# BPW5011-SPI-ADC.net
KiCad netlist of a schematic drawn in EAGLE
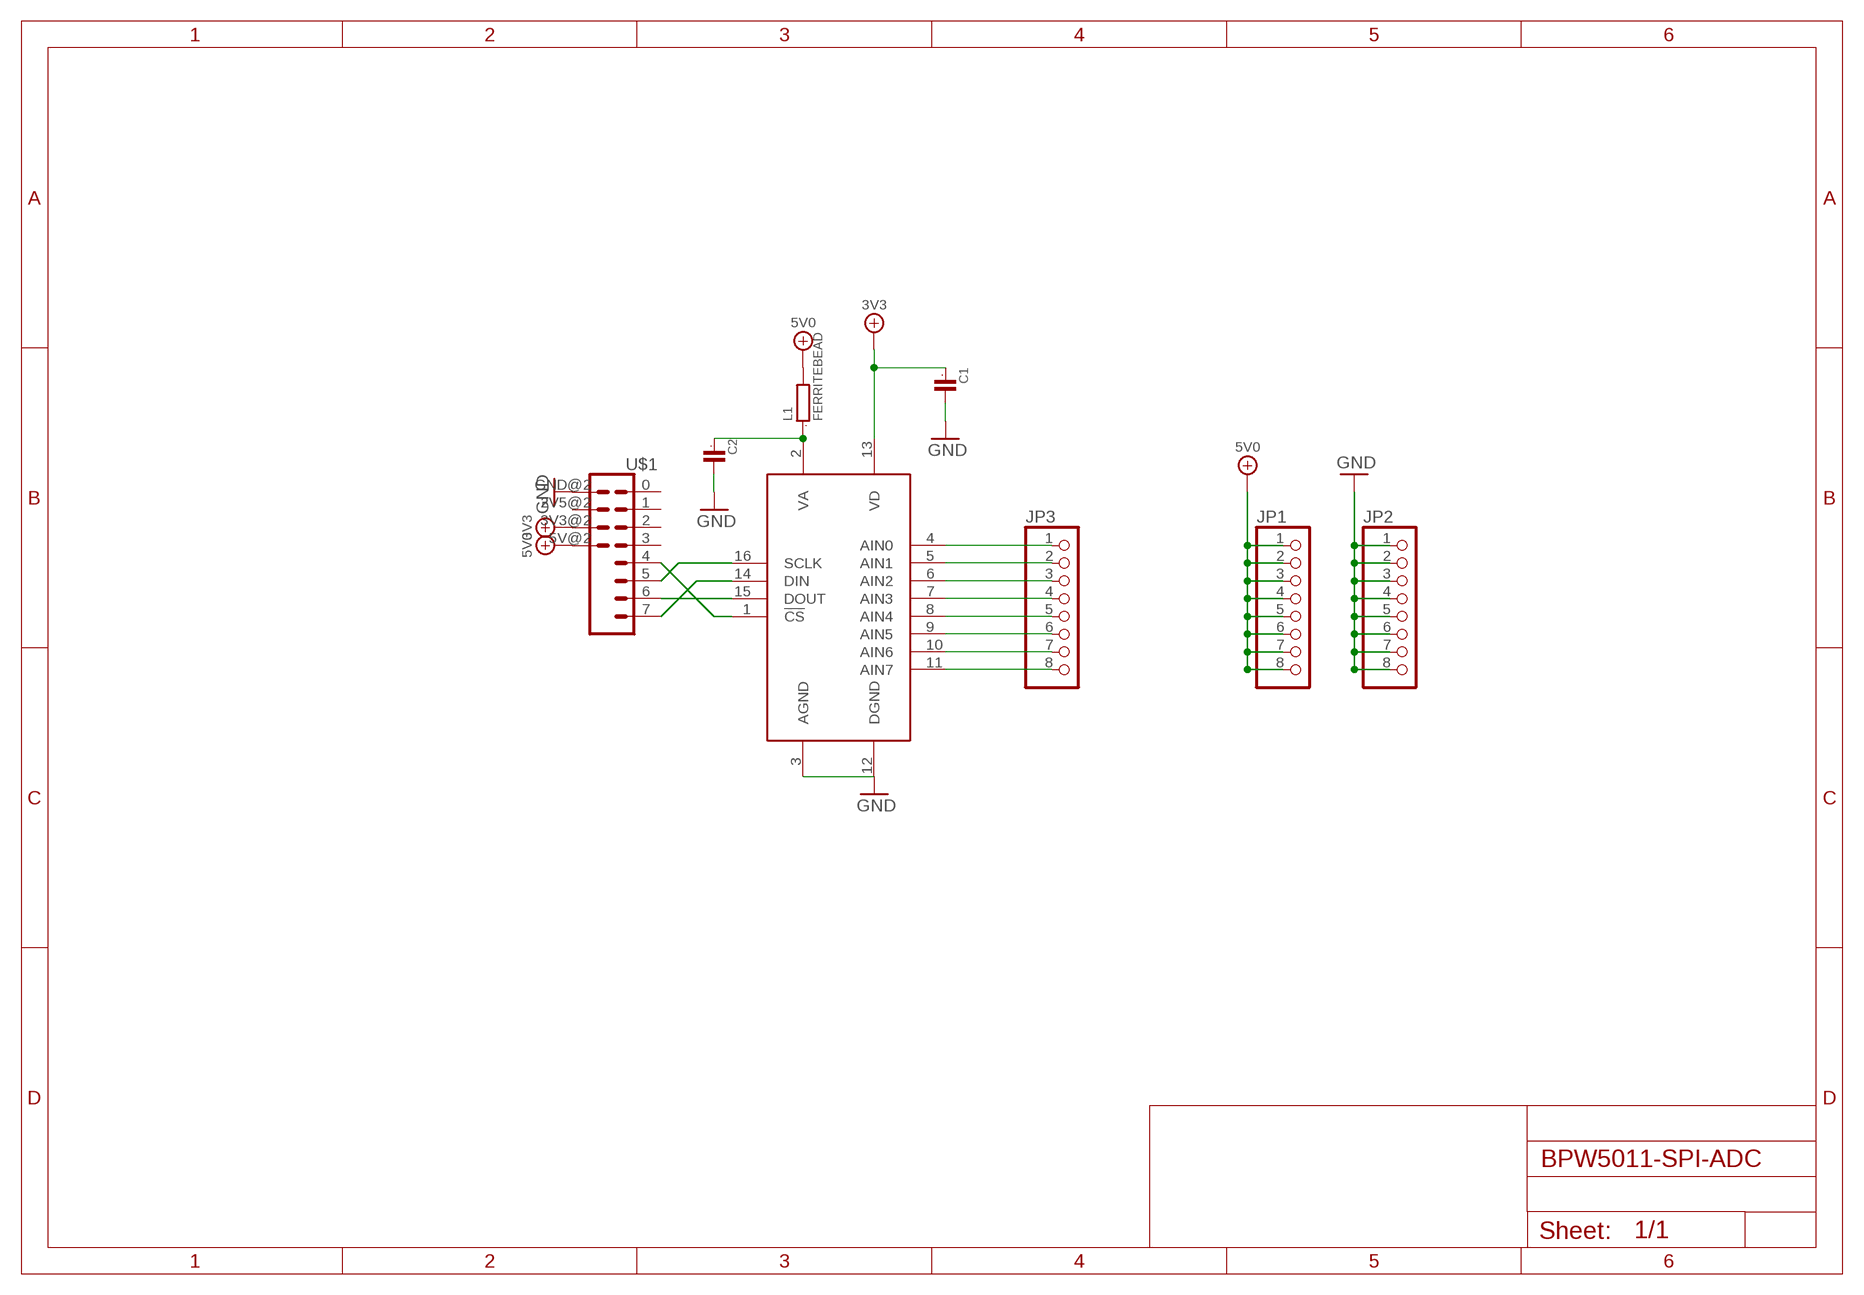
[diagram p0: schematic, sheet 1]

(export (version "E")
  (design (tool "Eeschema 10.0.6"))
  (components
    (comp (ref "C1")
      (value "C0603")
      (footprint "eagle-import:0603")
      (libsource (lib "eagle-import") (part "C0603"))
    )
    (comp (ref "C2")
      (value "C0603")
      (footprint "eagle-import:0603")
      (libsource (lib "eagle-import") (part "C0603"))
    )
    (comp (ref "JP1")
      (value "PINHD-1X8")
      (footprint "eagle-import:1X08")
      (libsource (lib "eagle-import") (part "PINHD-1X8"))
    )
    (comp (ref "JP2")
      (value "PINHD-1X8")
      (footprint "eagle-import:1X08")
      (libsource (lib "eagle-import") (part "PINHD-1X8"))
    )
    (comp (ref "JP3")
      (value "PINHD-1X8")
      (footprint "eagle-import:1X08")
      (libsource (lib "eagle-import") (part "PINHD-1X8"))
    )
    (comp (ref "L1")
      (value "FERRITEBEAD")
      (footprint "eagle-import:0603")
      (libsource (lib "eagle-import") (part "R0603"))
    )
    (comp (ref "U$1")
      (value "WING8WING8_NOHOLES")
      (footprint "eagle-import:WINGSIDE_8BIT_NOHOLES")
      (libsource (lib "eagle-import") (part "WING8WING8_NOHOLES"))
    )
    (comp (ref "U1")
      (value "ADC088S102CIMT")
      (footprint "eagle-import:TSSOP16")
      (libsource (lib "eagle-import") (part "ADC088S102CIMT"))
    )
  )
  (nets
    (net (code "1") (name "3V3") (class "Default")
      (node (ref "C1") (pin "1") (pinfunction "1_1") (pintype "passive"))
      (node (ref "U$1") (pin "3V3@2") (pinfunction "3V3_3V3@2") (pintype "passive"))
      (node (ref "U1") (pin "13") (pinfunction "VD_13") (pintype "power_in"))
    )
    (net (code "2") (name "5V0") (class "Default")
      (node (ref "JP1") (pin "1") (pinfunction "1_1") (pintype "passive"))
      (node (ref "JP1") (pin "2") (pinfunction "2_2") (pintype "passive"))
      (node (ref "JP1") (pin "3") (pinfunction "3_3") (pintype "passive"))
      (node (ref "JP1") (pin "4") (pinfunction "4_4") (pintype "passive"))
      (node (ref "JP1") (pin "5") (pinfunction "5_5") (pintype "passive"))
      (node (ref "JP1") (pin "6") (pinfunction "6_6") (pintype "passive"))
      (node (ref "JP1") (pin "7") (pinfunction "7_7") (pintype "passive"))
      (node (ref "JP1") (pin "8") (pinfunction "8_8") (pintype "passive"))
      (node (ref "L1") (pin "2") (pinfunction "2_2") (pintype "passive"))
      (node (ref "U$1") (pin "5V@2") (pinfunction "5V_5V@2") (pintype "passive"))
    )
    (net (code "3") (name "GND") (class "Default")
      (node (ref "C1") (pin "2") (pinfunction "2_2") (pintype "passive"))
      (node (ref "C2") (pin "2") (pinfunction "2_2") (pintype "passive"))
      (node (ref "JP2") (pin "1") (pinfunction "1_1") (pintype "passive"))
      (node (ref "JP2") (pin "2") (pinfunction "2_2") (pintype "passive"))
      (node (ref "JP2") (pin "3") (pinfunction "3_3") (pintype "passive"))
      (node (ref "JP2") (pin "4") (pinfunction "4_4") (pintype "passive"))
      (node (ref "JP2") (pin "5") (pinfunction "5_5") (pintype "passive"))
      (node (ref "JP2") (pin "6") (pinfunction "6_6") (pintype "passive"))
      (node (ref "JP2") (pin "7") (pinfunction "7_7") (pintype "passive"))
      (node (ref "JP2") (pin "8") (pinfunction "8_8") (pintype "passive"))
      (node (ref "U$1") (pin "GND@2") (pinfunction "GND_GND@2") (pintype "passive"))
      (node (ref "U1") (pin "12") (pinfunction "DGND_12") (pintype "power_in"))
      (node (ref "U1") (pin "3") (pinfunction "AGND_3") (pintype "power_in"))
    )
    (net (code "4") (name "Net-(U$1-5)") (class "Default")
      (node (ref "U$1") (pin "4") (pinfunction "5_4") (pintype "passive"))
      (node (ref "U1") (pin "1") (pinfunction "~{CS}_1") (pintype "input"))
    )
    (net (code "5") (name "Net-(U$1-6)") (class "Default")
      (node (ref "U$1") (pin "5") (pinfunction "6_5") (pintype "passive"))
      (node (ref "U1") (pin "16") (pinfunction "SCLK_16") (pintype "input"))
    )
    (net (code "6") (name "Net-(U$1-7)") (class "Default")
      (node (ref "U$1") (pin "6") (pinfunction "7_6") (pintype "passive"))
      (node (ref "U1") (pin "15") (pinfunction "DOUT_15") (pintype "output"))
    )
    (net (code "7") (name "Net-(U$1-8)") (class "Default")
      (node (ref "U$1") (pin "7") (pinfunction "8_7") (pintype "passive"))
      (node (ref "U1") (pin "14") (pinfunction "DIN_14") (pintype "input"))
    )
    (net (code "8") (name "Net-(U1-AIN0)") (class "Default")
      (node (ref "JP3") (pin "1") (pinfunction "1_1") (pintype "passive"))
      (node (ref "U1") (pin "4") (pinfunction "AIN0_4") (pintype "input"))
    )
    (net (code "9") (name "Net-(U1-AIN1)") (class "Default")
      (node (ref "JP3") (pin "2") (pinfunction "2_2") (pintype "passive"))
      (node (ref "U1") (pin "5") (pinfunction "AIN1_5") (pintype "input"))
    )
    (net (code "10") (name "Net-(U1-AIN2)") (class "Default")
      (node (ref "JP3") (pin "3") (pinfunction "3_3") (pintype "passive"))
      (node (ref "U1") (pin "6") (pinfunction "AIN2_6") (pintype "input"))
    )
    (net (code "11") (name "Net-(U1-AIN3)") (class "Default")
      (node (ref "JP3") (pin "4") (pinfunction "4_4") (pintype "passive"))
      (node (ref "U1") (pin "7") (pinfunction "AIN3_7") (pintype "input"))
    )
    (net (code "12") (name "Net-(U1-AIN4)") (class "Default")
      (node (ref "JP3") (pin "5") (pinfunction "5_5") (pintype "passive"))
      (node (ref "U1") (pin "8") (pinfunction "AIN4_8") (pintype "input"))
    )
    (net (code "13") (name "Net-(U1-AIN5)") (class "Default")
      (node (ref "JP3") (pin "6") (pinfunction "6_6") (pintype "passive"))
      (node (ref "U1") (pin "9") (pinfunction "AIN5_9") (pintype "input"))
    )
    (net (code "14") (name "Net-(U1-AIN6)") (class "Default")
      (node (ref "JP3") (pin "7") (pinfunction "7_7") (pintype "passive"))
      (node (ref "U1") (pin "10") (pinfunction "AIN6_10") (pintype "input"))
    )
    (net (code "15") (name "Net-(U1-AIN7)") (class "Default")
      (node (ref "JP3") (pin "8") (pinfunction "8_8") (pintype "passive"))
      (node (ref "U1") (pin "11") (pinfunction "AIN7_11") (pintype "input"))
    )
    (net (code "16") (name "Net-(U1-VA)") (class "Default")
      (node (ref "C2") (pin "1") (pinfunction "1_1") (pintype "passive"))
      (node (ref "L1") (pin "1") (pinfunction "1_1") (pintype "passive"))
      (node (ref "U1") (pin "2") (pinfunction "VA_2") (pintype "power_in"))
    )
    (net (code "17") (name "unconnected-(U$1-1-Pad0)") (class "Default")
      (node (ref "U$1") (pin "0") (pinfunction "1_0") (pintype "passive"))
    )
    (net (code "18") (name "unconnected-(U$1-2-Pad1)") (class "Default")
      (node (ref "U$1") (pin "1") (pinfunction "2_1") (pintype "passive"))
    )
    (net (code "19") (name "unconnected-(U$1-2V5-Pad2V5@2)") (class "Default")
      (node (ref "U$1") (pin "2V5@2") (pinfunction "2V5_2V5@2") (pintype "passive"))
    )
    (net (code "20") (name "unconnected-(U$1-3-Pad2)") (class "Default")
      (node (ref "U$1") (pin "2") (pinfunction "3_2") (pintype "passive"))
    )
    (net (code "21") (name "unconnected-(U$1-4-Pad3)") (class "Default")
      (node (ref "U$1") (pin "3") (pinfunction "4_3") (pintype "passive"))
    )
  )
)
